# led-esp32.net
KiCad netlist of a schematic drawn in Altium Designer
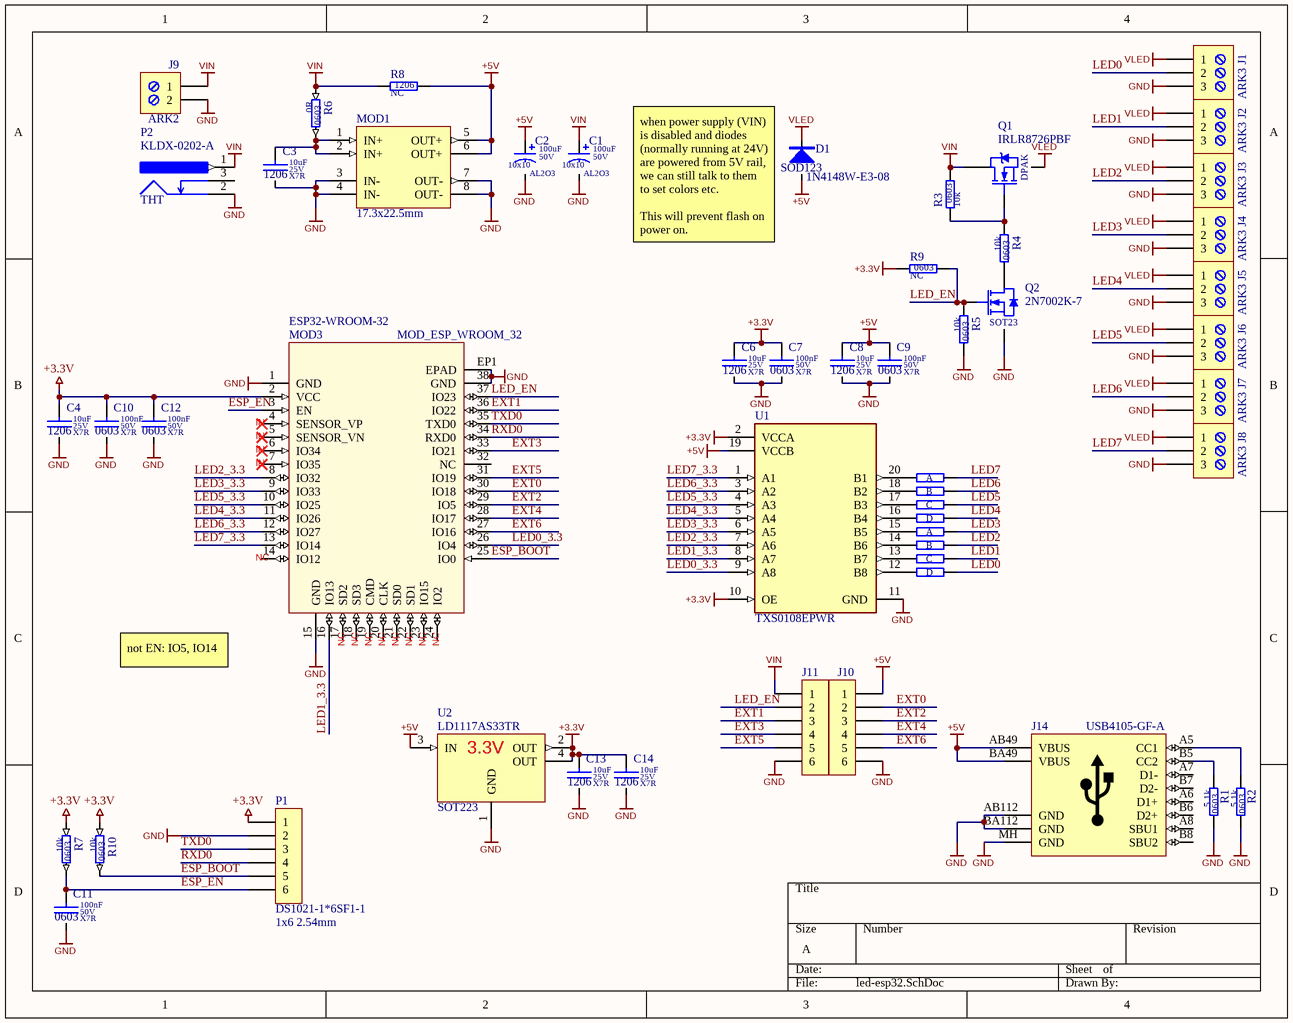
[diagram p0: led-esp32.SchDoc]

(export (version "E")
  (design (tool "Eeschema 10.0.6"))
  (components
    (comp (ref "C1")
      (value "100uF")
      (footprint "CE_D_10x10_SMD")
      (description "Polarized Capacitor")
      (fields
        (field (name "DIELECTRIC") "AL2O3")
        (field (name "SCH_FOOTPRINT") "10x10")
        (field (name "VOLTAGE") "50V")
        (field (name "PART NUMBER") "CE_100uF_50V_AL2O3_10x10_20")
        (field (name "MANUFACTURER") "Nichicon")
      )
      (libsource (lib "Library") (part "CE"))
    )
    (comp (ref "C2")
      (value "100uF")
      (footprint "CE_D_10x10_SMD")
      (description "Polarized Capacitor")
      (fields
        (field (name "DIELECTRIC") "AL2O3")
        (field (name "SCH_FOOTPRINT") "10x10")
        (field (name "VOLTAGE") "50V")
        (field (name "PART NUMBER") "CE_100uF_50V_AL2O3_10x10_20")
        (field (name "MANUFACTURER") "Nichicon")
      )
      (libsource (lib "Library") (part "CE"))
    )
    (comp (ref "C3")
      (value "10uF")
      (footprint "C_1206_3216")
      (description "Capacitor")
      (fields
        (field (name "DIELECTRIC") "X7R")
        (field (name "VOLTAGE") "25V")
        (field (name "SCH_FOOTPRINT") "1206")
        (field (name "PART NUMBER") "C_10uF_25V_X7R_1206_10")
        (field (name "MANUFACTURER") "Samsung")
      )
      (libsource (lib "Library") (part "C"))
    )
    (comp (ref "C4")
      (value "10uF")
      (footprint "C_1206_3216")
      (description "Capacitor")
      (fields
        (field (name "DIELECTRIC") "X7R")
        (field (name "VOLTAGE") "25V")
        (field (name "SCH_FOOTPRINT") "1206")
        (field (name "PART NUMBER") "C_10uF_25V_X7R_1206_10")
        (field (name "MANUFACTURER") "Samsung")
      )
      (libsource (lib "Library") (part "C"))
    )
    (comp (ref "C6")
      (value "10uF")
      (footprint "C_1206_3216")
      (description "Capacitor")
      (fields
        (field (name "DIELECTRIC") "X7R")
        (field (name "VOLTAGE") "25V")
        (field (name "SCH_FOOTPRINT") "1206")
        (field (name "PART NUMBER") "C_10uF_25V_X7R_1206_10")
        (field (name "MANUFACTURER") "Samsung")
      )
      (libsource (lib "Library") (part "C"))
    )
    (comp (ref "C7")
      (value "100nF")
      (footprint "C_0603_1608")
      (description "Capacitor")
      (fields
        (field (name "DIELECTRIC") "X7R")
        (field (name "VOLTAGE") "50V")
        (field (name "SCH_FOOTPRINT") "0603")
        (field (name "PART NUMBER") "C_100nF_50V_X7R_0603_5")
        (field (name "MANUFACTURER") "Samsung")
      )
      (libsource (lib "Library") (part "C"))
    )
    (comp (ref "C8")
      (value "10uF")
      (footprint "C_1206_3216")
      (description "Capacitor")
      (fields
        (field (name "DIELECTRIC") "X7R")
        (field (name "VOLTAGE") "25V")
        (field (name "SCH_FOOTPRINT") "1206")
        (field (name "PART NUMBER") "C_10uF_25V_X7R_1206_10")
        (field (name "MANUFACTURER") "Samsung")
      )
      (libsource (lib "Library") (part "C"))
    )
    (comp (ref "C9")
      (value "100nF")
      (footprint "C_0603_1608")
      (description "Capacitor")
      (fields
        (field (name "DIELECTRIC") "X7R")
        (field (name "VOLTAGE") "50V")
        (field (name "SCH_FOOTPRINT") "0603")
        (field (name "PART NUMBER") "C_100nF_50V_X7R_0603_5")
        (field (name "MANUFACTURER") "Samsung")
      )
      (libsource (lib "Library") (part "C"))
    )
    (comp (ref "C10")
      (value "100nF")
      (footprint "C_0603_1608")
      (description "Capacitor")
      (fields
        (field (name "DIELECTRIC") "X7R")
        (field (name "VOLTAGE") "50V")
        (field (name "SCH_FOOTPRINT") "0603")
        (field (name "PART NUMBER") "C_100nF_50V_X7R_0603_5")
        (field (name "MANUFACTURER") "Samsung")
      )
      (libsource (lib "Library") (part "C"))
    )
    (comp (ref "C11")
      (value "100nF")
      (footprint "C_0603_1608")
      (description "Capacitor")
      (fields
        (field (name "DIELECTRIC") "X7R")
        (field (name "VOLTAGE") "50V")
        (field (name "SCH_FOOTPRINT") "0603")
        (field (name "PART NUMBER") "C_100nF_50V_X7R_0603_5")
        (field (name "MANUFACTURER") "Samsung")
      )
      (libsource (lib "Library") (part "C"))
    )
    (comp (ref "C12")
      (value "100nF")
      (footprint "C_0603_1608")
      (description "Capacitor")
      (fields
        (field (name "DIELECTRIC") "X7R")
        (field (name "VOLTAGE") "50V")
        (field (name "SCH_FOOTPRINT") "0603")
        (field (name "PART NUMBER") "C_100nF_50V_X7R_0603_5")
        (field (name "MANUFACTURER") "Samsung")
      )
      (libsource (lib "Library") (part "C"))
    )
    (comp (ref "C13")
      (value "10uF")
      (footprint "C_1206_3216")
      (description "Capacitor")
      (fields
        (field (name "DIELECTRIC") "X7R")
        (field (name "VOLTAGE") "25V")
        (field (name "SCH_FOOTPRINT") "1206")
        (field (name "PART NUMBER") "C_10uF_25V_X7R_1206_10")
        (field (name "MANUFACTURER") "Samsung")
      )
      (libsource (lib "Library") (part "C"))
    )
    (comp (ref "C14")
      (value "10uF")
      (footprint "C_1206_3216")
      (description "Capacitor")
      (fields
        (field (name "DIELECTRIC") "X7R")
        (field (name "VOLTAGE") "25V")
        (field (name "SCH_FOOTPRINT") "1206")
        (field (name "PART NUMBER") "C_10uF_25V_X7R_1206_10")
        (field (name "MANUFACTURER") "Samsung")
      )
      (libsource (lib "Library") (part "C"))
    )
    (comp (ref "D1")
      (value "1N4148W-E3-08")
      (footprint "SOD123")
      (fields
        (field (name "SCH_FOOTPRINT") "SOD123")
        (field (name "PART NUMBER") "D_1N4148W_0A15_75V_SOD123")
        (field (name "VOLTAGE") "75")
        (field (name "MANUFACTURER") "Vishay")
      )
      (libsource (lib "Library") (part "D"))
    )
    (comp (ref "J1")
      (value "ARK3")
      (footprint "J_ARK3")
      (description "ARK Screw terminal, 3-Pin")
      (fields
        (field (name "SCH_FOOTPRINT") "ARK3")
        (field (name "PART NUMBER") "J_TB-5.0-P-3P")
        (field (name "MANUFACTURER") "DEGSON ELECTRONICS")
      )
      (libsource (lib "Library") (part "J_ARK3"))
    )
    (comp (ref "J2")
      (value "ARK3")
      (footprint "J_ARK3")
      (description "ARK Screw terminal, 3-Pin")
      (fields
        (field (name "SCH_FOOTPRINT") "ARK3")
        (field (name "PART NUMBER") "J_TB-5.0-P-3P")
        (field (name "MANUFACTURER") "DEGSON ELECTRONICS")
      )
      (libsource (lib "Library") (part "J_ARK3"))
    )
    (comp (ref "J3")
      (value "ARK3")
      (footprint "J_ARK3")
      (description "ARK Screw terminal, 3-Pin")
      (fields
        (field (name "SCH_FOOTPRINT") "ARK3")
        (field (name "PART NUMBER") "J_TB-5.0-P-3P")
        (field (name "MANUFACTURER") "DEGSON ELECTRONICS")
      )
      (libsource (lib "Library") (part "J_ARK3"))
    )
    (comp (ref "J4")
      (value "ARK3")
      (footprint "J_ARK3")
      (description "ARK Screw terminal, 3-Pin")
      (fields
        (field (name "SCH_FOOTPRINT") "ARK3")
        (field (name "PART NUMBER") "J_TB-5.0-P-3P")
        (field (name "MANUFACTURER") "DEGSON ELECTRONICS")
      )
      (libsource (lib "Library") (part "J_ARK3"))
    )
    (comp (ref "J5")
      (value "ARK3")
      (footprint "J_ARK3")
      (description "ARK Screw terminal, 3-Pin")
      (fields
        (field (name "SCH_FOOTPRINT") "ARK3")
        (field (name "PART NUMBER") "J_TB-5.0-P-3P")
        (field (name "MANUFACTURER") "DEGSON ELECTRONICS")
      )
      (libsource (lib "Library") (part "J_ARK3"))
    )
    (comp (ref "J6")
      (value "ARK3")
      (footprint "J_ARK3")
      (description "ARK Screw terminal, 3-Pin")
      (fields
        (field (name "SCH_FOOTPRINT") "ARK3")
        (field (name "PART NUMBER") "J_TB-5.0-P-3P")
        (field (name "MANUFACTURER") "DEGSON ELECTRONICS")
      )
      (libsource (lib "Library") (part "J_ARK3"))
    )
    (comp (ref "J7")
      (value "ARK3")
      (footprint "J_ARK3")
      (description "ARK Screw terminal, 3-Pin")
      (fields
        (field (name "SCH_FOOTPRINT") "ARK3")
        (field (name "PART NUMBER") "J_TB-5.0-P-3P")
        (field (name "MANUFACTURER") "DEGSON ELECTRONICS")
      )
      (libsource (lib "Library") (part "J_ARK3"))
    )
    (comp (ref "J8")
      (value "ARK3")
      (footprint "J_ARK3")
      (description "ARK Screw terminal, 3-Pin")
      (fields
        (field (name "SCH_FOOTPRINT") "ARK3")
        (field (name "PART NUMBER") "J_TB-5.0-P-3P")
        (field (name "MANUFACTURER") "DEGSON ELECTRONICS")
      )
      (libsource (lib "Library") (part "J_ARK3"))
    )
    (comp (ref "J9")
      (value "ARK2")
      (footprint "J_ARK2")
      (description "ARK Screw terminal, 2-Pin")
      (fields
        (field (name "SCH_FOOTPRINT") "ARK2")
        (field (name "PART NUMBER") "J_TB-5.0-P-2P")
        (field (name "MANUFACTURER") "DEGSON ELECTRONICS")
      )
      (libsource (lib "Library") (part "J_ARK2"))
    )
    (comp (ref "J10")
      (value "Goldpin female straight")
      (footprint "J_HEADER_1x6_2.54_VERTICAL")
      (description "Pin Header")
      (fields
        (field (name "PART NUMBER") "J_HEADER_1x6_2.54_VERTICAL")
        (field (name "MANUFACTURER") "Connfly")
      )
      (libsource (lib "Library") (part "J_HEADER_1x6"))
    )
    (comp (ref "J11")
      (value "Goldpin female straight")
      (footprint "J_HEADER_1x6_2.54_VERTICAL")
      (description "Pin Header")
      (fields
        (field (name "PART NUMBER") "J_HEADER_1x6_2.54_VERTICAL")
        (field (name "MANUFACTURER") "Connfly")
      )
      (libsource (lib "") (part "J_HEADER_1x6_1"))
    )
    (comp (ref "J14")
      (value "USB4105-GF-A")
      (footprint "J_USB_C_USB4105")
      (fields
        (field (name "PART NUMBER") "J_USB_C_USB4105-GF-A")
        (field (name "MANUFACTURER") "GCT")
        (field (name "Comment") "USB C Connector")
      )
      (libsource (lib "Library") (part "J_USB_C_2.0_USB4105"))
    )
    (comp (ref "MOD1")
      (value "Low cost, Aliexpress-ready DC-DC buck converter using MP1584")
      (footprint "MOD_BUCK_MP1584")
      (fields (field (name "SCH_FOOTPRINT") "17.3x22.5mm") (field (name "PART NUMBER") "MOD_BUCK_MP1584"))
      (libsource (lib "Library") (part "MOD_BUCK_MP1584"))
    )
    (comp (ref "MOD3")
      (value "ESP32-WROOM-32")
      (footprint "MOD_ESP_WROOM_32")
      (fields
        (field (name "SCH_FOOTPRINT") "MOD_ESP_WROOM_32")
        (field (name "PART NUMBER") "MOD_ESP32-WROOM-32")
        (field (name "MANUFACTURER") "ESPRESSIF")
        (field (name "Comment") "2.4 GHz Wi-Fi-and-Bluetooth combo chip")
      )
      (libsource (lib "Library") (part "MOD_ESP_WROOM_32"))
    )
    (comp (ref "P1")
      (value "DS1021-1*6SF1-1")
      (footprint "P_HEADER_1x6_2.54")
      (description "Pin Header")
      (fields
        (field (name "PART NUMBER") "P_HEADER_1x6_2.54")
        (field (name "SCH_FOOTPRINT") "1x6 2.54mm")
        (field (name "MANUFACTURER") "Connfly")
      )
      (libsource (lib "Library") (part "P_HEADER_1x6"))
    )
    (comp (ref "P2")
      (value "KLDX-0202-A")
      (footprint "P_KLDX-0202-A")
      (description "Typical 3-pin jack power connector with switch")
      (fields
        (field (name "SCH_FOOTPRINT") "THT")
        (field (name "PART NUMBER") "P_KLDX-0202-A")
        (field (name "MANUFACTURER") "Kycon")
      )
      (libsource (lib "Library") (part "P_DC_JACK"))
    )
    (comp (ref "Q1")
      (value "IRLR8726PBF")
      (footprint "DPAK_TO252-3_SC63_M")
      (fields
        (field (name "SCH_FOOTPRINT") "DPAK")
        (field (name "PART NUMBER") "QNS_IRLR8726PBF")
        (field (name "VOLTAGE") "30V")
        (field (name "MANUFACTURER") "Infineon")
      )
      (libsource (lib "Library") (part "QNS_GDS"))
    )
    (comp (ref "Q2")
      (value "2N7002K-7")
      (footprint "SOT23_TO236_SC59")
      (fields
        (field (name "SCH_FOOTPRINT") "SOT23")
        (field (name "PART NUMBER") "QN_2N7002K-7")
        (field (name "VOLTAGE") "60V")
        (field (name "MANUFACTURER") "Diodes Inc")
      )
      (libsource (lib "Library") (part "QN_GSD"))
    )
    (comp (ref "R1")
      (value "5.1k")
      (footprint "R_0603_1608")
      (fields
        (field (name "SCH_FOOTPRINT") "0603")
        (field (name "PART NUMBER") "R_5.1k_0603_1")
        (field (name "VOLTAGE") "75V")
        (field (name "POWER") "100mW")
      )
      (libsource (lib "") (part "R_1"))
    )
    (comp (ref "R2")
      (value "5.1k")
      (footprint "R_0603_1608")
      (fields
        (field (name "SCH_FOOTPRINT") "0603")
        (field (name "PART NUMBER") "R_5.1k_0603_1")
        (field (name "VOLTAGE") "75V")
        (field (name "POWER") "100mW")
      )
      (libsource (lib "") (part "R_1"))
    )
    (comp (ref "R3")
      (value "10k")
      (footprint "R_0603_1608")
      (fields
        (field (name "SCH_FOOTPRINT") "0603")
        (field (name "PART NUMBER") "R_10k_0603_1")
        (field (name "VOLTAGE") "75V")
        (field (name "POWER") "100mW")
      )
      (libsource (lib "") (part "R_1"))
    )
    (comp (ref "R4")
      (value "10k")
      (footprint "R_0603_1608")
      (fields
        (field (name "SCH_FOOTPRINT") "0603")
        (field (name "PART NUMBER") "R_10k_0603_1")
        (field (name "VOLTAGE") "75V")
        (field (name "POWER") "100mW")
      )
      (libsource (lib "") (part "R_1"))
    )
    (comp (ref "R5")
      (value "10k")
      (footprint "R_0603_1608")
      (fields
        (field (name "SCH_FOOTPRINT") "0603")
        (field (name "PART NUMBER") "R_10k_0603_1")
        (field (name "VOLTAGE") "75V")
        (field (name "POWER") "100mW")
      )
      (libsource (lib "") (part "R_1"))
    )
    (comp (ref "R6")
      (value "0R")
      (footprint "R_0603_1608")
      (fields
        (field (name "SCH_FOOTPRINT") "0603")
        (field (name "PART NUMBER") "R_0R_0603_1")
        (field (name "VOLTAGE") "75V")
        (field (name "POWER") "100mW")
      )
      (libsource (lib "Library") (part "R"))
    )
    (comp (ref "R7")
      (value "10k")
      (footprint "R_0603_1608")
      (fields
        (field (name "SCH_FOOTPRINT") "0603")
        (field (name "PART NUMBER") "R_10k_0603_1_AECQ0")
        (field (name "VOLTAGE") "75V")
        (field (name "POWER") "100mW")
      )
      (libsource (lib "Library") (part "R"))
    )
    (comp (ref "R8")
      (value "NC")
      (footprint "R_NC_1206_3216")
      (fields
        (field (name "SCH_FOOTPRINT") "1206")
        (field (name "PART NUMBER") "R_GENERIC_1206")
        (field (name "Comment") "Resistor")
      )
      (libsource (lib "") (part "R_1"))
    )
    (comp (ref "R9")
      (value "NC")
      (footprint "R_NC_0603_1608")
      (fields
        (field (name "SCH_FOOTPRINT") "0603")
        (field (name "PART NUMBER") "R_GENERIC_0603")
        (field (name "Comment") "Resistor")
      )
      (libsource (lib "") (part "R_1"))
    )
    (comp (ref "R10")
      (value "10k")
      (footprint "R_0603_1608")
      (fields
        (field (name "SCH_FOOTPRINT") "0603")
        (field (name "PART NUMBER") "R_10k_0603_1_AECQ0")
        (field (name "VOLTAGE") "75V")
        (field (name "POWER") "100mW")
      )
      (libsource (lib "Library") (part "R"))
    )
    (comp (ref "RN1")
      (value "Resistors Network")
      (footprint "RN4_0804_2010")
      (fields
        (field (name "PART NUMBER") "RN4_120R_0804_5")
        (field (name "VOLTAGE") "50V")
        (field (name "POWER") "63mW")
      )
      (libsource (lib "Library") (part "RN4"))
    )
    (comp (ref "RN2")
      (value "Resistors Network")
      (footprint "RN4_0804_2010")
      (fields
        (field (name "PART NUMBER") "RN4_120R_0804_5")
        (field (name "VOLTAGE") "50V")
        (field (name "POWER") "63mW")
      )
      (libsource (lib "Library") (part "RN4"))
    )
    (comp (ref "U1")
      (value "TXS0108EPWR")
      (footprint "FP-PW0020A-IPC_C")
      (description "IC TRNSLTR BIDIRECTIONAL 20TSSOP")
      (libsource (lib "Altium Content Vault") (part "86128ddf5852d4e934b2dd0188c13f1"))
    )
    (comp (ref "U2")
      (value "LD1117AS33TR")
      (footprint "SOT223_SC73")
      (description "typical configuration")
      (fields
        (field (name "SCH_FOOTPRINT") "SOT223")
        (field (name "PART NUMBER") "VL_LD1117AS33TR_3V3_1A2")
        (field (name "VOLTAGE") "3.3V")
      )
      (libsource (lib "Library") (part "VL_4pin_3_1_2,4"))
    )
  )
  (nets
    (net (code "1") (name "+3.3V") (class "Default")
      (node (ref "C10") (pin "1") (pinfunction "1_1") (pintype "passive"))
      (node (ref "C12") (pin "1") (pinfunction "1_1") (pintype "passive"))
      (node (ref "C13") (pin "1") (pinfunction "1_1") (pintype "passive"))
      (node (ref "C14") (pin "1") (pinfunction "1_1") (pintype "passive"))
      (node (ref "C4") (pin "1") (pinfunction "1_1") (pintype "passive"))
      (node (ref "C6") (pin "1") (pinfunction "1_1") (pintype "passive"))
      (node (ref "C7") (pin "1") (pinfunction "1_1") (pintype "passive"))
      (node (ref "MOD3") (pin "2") (pinfunction "VCC_2") (pintype "input"))
      (node (ref "P1") (pin "1") (pinfunction "1_1") (pintype "passive"))
      (node (ref "R10") (pin "1") (pinfunction "1_1") (pintype "input"))
      (node (ref "R7") (pin "1") (pinfunction "1_1") (pintype "input"))
      (node (ref "R9") (pin "1") (pinfunction "1_1") (pintype "passive"))
      (node (ref "U1") (pin "10") (pinfunction "OE_10") (pintype "input"))
      (node (ref "U1") (pin "2") (pinfunction "VCCA_2") (pintype "power_in"))
      (node (ref "U2") (pin "2") (pinfunction "OUT_2") (pintype "output"))
      (node (ref "U2") (pin "4") (pinfunction "OUT_4") (pintype "passive"))
    )
    (net (code "2") (name "+5V") (class "Default")
      (node (ref "C2") (pin "1") (pinfunction "1_1") (pintype "passive"))
      (node (ref "C8") (pin "1") (pinfunction "1_1") (pintype "passive"))
      (node (ref "C9") (pin "1") (pinfunction "1_1") (pintype "passive"))
      (node (ref "D1") (pin "2") (pintype "passive"))
      (node (ref "J10") (pin "1") (pinfunction "1_1") (pintype "passive"))
      (node (ref "J14") (pin "AB49") (pinfunction "VBUS_AB49") (pintype "power_in"))
      (node (ref "J14") (pin "BA49") (pinfunction "VBUS_BA49") (pintype "power_in"))
      (node (ref "MOD1") (pin "5") (pinfunction "OUT+_5") (pintype "output"))
      (node (ref "MOD1") (pin "6") (pinfunction "OUT+_6") (pintype "passive"))
      (node (ref "R8") (pin "2") (pinfunction "2_2") (pintype "passive"))
      (node (ref "U1") (pin "19") (pinfunction "VCCB_19") (pintype "power_in"))
      (node (ref "U2") (pin "3") (pinfunction "IN_3") (pintype "input"))
    )
    (net (code "3") (name "/ESP_BOOT") (class "Default")
      (node (ref "MOD3") (pin "25") (pinfunction "IO0_25") (pintype "input"))
      (node (ref "P1") (pin "5") (pinfunction "5_5") (pintype "passive"))
      (node (ref "R10") (pin "2") (pinfunction "2_2") (pintype "output"))
    )
    (net (code "4") (name "/ESP_EN") (class "Default")
      (node (ref "C11") (pin "1") (pinfunction "1_1") (pintype "passive"))
      (node (ref "MOD3") (pin "3") (pinfunction "EN_3") (pintype "input"))
      (node (ref "P1") (pin "6") (pinfunction "6_6") (pintype "passive"))
      (node (ref "R7") (pin "2") (pinfunction "2_2") (pintype "output"))
    )
    (net (code "5") (name "/EXT0") (class "Default")
      (node (ref "J10") (pin "2") (pinfunction "2_2") (pintype "passive"))
      (node (ref "MOD3") (pin "30") (pinfunction "IO18_30") (pintype "bidirectional"))
    )
    (net (code "6") (name "/EXT1") (class "Default")
      (node (ref "J11") (pin "3") (pinfunction "3_3") (pintype "passive"))
      (node (ref "MOD3") (pin "36") (pinfunction "IO22_36") (pintype "bidirectional"))
    )
    (net (code "7") (name "/EXT2") (class "Default")
      (node (ref "J10") (pin "3") (pinfunction "3_3") (pintype "passive"))
      (node (ref "MOD3") (pin "29") (pinfunction "IO5_29") (pintype "bidirectional"))
    )
    (net (code "8") (name "/EXT3") (class "Default")
      (node (ref "J11") (pin "4") (pinfunction "4_4") (pintype "passive"))
      (node (ref "MOD3") (pin "33") (pinfunction "IO21_33") (pintype "bidirectional"))
    )
    (net (code "9") (name "/EXT4") (class "Default")
      (node (ref "J10") (pin "4") (pinfunction "4_4") (pintype "passive"))
      (node (ref "MOD3") (pin "28") (pinfunction "IO17_28") (pintype "bidirectional"))
    )
    (net (code "10") (name "/EXT5") (class "Default")
      (node (ref "J11") (pin "5") (pinfunction "5_5") (pintype "passive"))
      (node (ref "MOD3") (pin "31") (pinfunction "IO19_31") (pintype "bidirectional"))
    )
    (net (code "11") (name "/EXT6") (class "Default")
      (node (ref "J10") (pin "5") (pinfunction "5_5") (pintype "passive"))
      (node (ref "MOD3") (pin "27") (pinfunction "IO16_27") (pintype "bidirectional"))
    )
    (net (code "12") (name "/LED0") (class "Default")
      (node (ref "J1") (pin "2") (pinfunction "2_2") (pintype "passive"))
      (node (ref "RN2") (pin "5") (pinfunction "5_5") (pintype "passive"))
    )
    (net (code "13") (name "/LED0_3.3") (class "Default")
      (node (ref "MOD3") (pin "26") (pinfunction "IO4_26") (pintype "bidirectional"))
      (node (ref "U1") (pin "9") (pinfunction "A8_9") (pintype "input"))
    )
    (net (code "14") (name "/LED1") (class "Default")
      (node (ref "J2") (pin "2") (pinfunction "2_2") (pintype "passive"))
      (node (ref "RN2") (pin "6") (pinfunction "6_6") (pintype "passive"))
    )
    (net (code "15") (name "/LED1_3.3") (class "Default")
      (node (ref "MOD3") (pin "16") (pinfunction "IO13_16") (pintype "bidirectional"))
      (node (ref "U1") (pin "8") (pinfunction "A7_8") (pintype "input"))
    )
    (net (code "16") (name "/LED2") (class "Default")
      (node (ref "J3") (pin "2") (pinfunction "2_2") (pintype "passive"))
      (node (ref "RN2") (pin "7") (pinfunction "7_7") (pintype "passive"))
    )
    (net (code "17") (name "/LED2_3.3") (class "Default")
      (node (ref "MOD3") (pin "8") (pinfunction "IO32_8") (pintype "bidirectional"))
      (node (ref "U1") (pin "7") (pinfunction "A6_7") (pintype "input"))
    )
    (net (code "18") (name "/LED3") (class "Default")
      (node (ref "J4") (pin "2") (pinfunction "2_2") (pintype "passive"))
      (node (ref "RN2") (pin "8") (pinfunction "8_8") (pintype "passive"))
    )
    (net (code "19") (name "/LED3_3.3") (class "Default")
      (node (ref "MOD3") (pin "9") (pinfunction "IO33_9") (pintype "bidirectional"))
      (node (ref "U1") (pin "6") (pinfunction "A5_6") (pintype "input"))
    )
    (net (code "20") (name "/LED4") (class "Default")
      (node (ref "J5") (pin "2") (pinfunction "2_2") (pintype "passive"))
      (node (ref "RN1") (pin "5") (pinfunction "5_5") (pintype "passive"))
    )
    (net (code "21") (name "/LED4_3.3") (class "Default")
      (node (ref "MOD3") (pin "11") (pinfunction "IO26_11") (pintype "bidirectional"))
      (node (ref "U1") (pin "5") (pinfunction "A4_5") (pintype "input"))
    )
    (net (code "22") (name "/LED5") (class "Default")
      (node (ref "J6") (pin "2") (pinfunction "2_2") (pintype "passive"))
      (node (ref "RN1") (pin "6") (pinfunction "6_6") (pintype "passive"))
    )
    (net (code "23") (name "/LED5_3.3") (class "Default")
      (node (ref "MOD3") (pin "10") (pinfunction "IO25_10") (pintype "bidirectional"))
      (node (ref "U1") (pin "4") (pinfunction "A3_4") (pintype "input"))
    )
    (net (code "24") (name "/LED6") (class "Default")
      (node (ref "J7") (pin "2") (pinfunction "2_2") (pintype "passive"))
      (node (ref "RN1") (pin "7") (pinfunction "7_7") (pintype "passive"))
    )
    (net (code "25") (name "/LED6_3.3") (class "Default")
      (node (ref "MOD3") (pin "12") (pinfunction "IO27_12") (pintype "bidirectional"))
      (node (ref "U1") (pin "3") (pinfunction "A2_3") (pintype "input"))
    )
    (net (code "26") (name "/LED7") (class "Default")
      (node (ref "J8") (pin "2") (pinfunction "2_2") (pintype "passive"))
      (node (ref "RN1") (pin "8") (pinfunction "8_8") (pintype "passive"))
    )
    (net (code "27") (name "/LED7_3.3") (class "Default")
      (node (ref "MOD3") (pin "13") (pinfunction "IO14_13") (pintype "bidirectional"))
      (node (ref "U1") (pin "1") (pinfunction "A1_1") (pintype "input"))
    )
    (net (code "28") (name "/LED_EN") (class "Default")
      (node (ref "J11") (pin "2") (pinfunction "2_2") (pintype "passive"))
      (node (ref "MOD3") (pin "37") (pinfunction "IO23_37") (pintype "bidirectional"))
      (node (ref "Q2") (pin "1") (pinfunction "G_1") (pintype "passive"))
      (node (ref "R5") (pin "1") (pinfunction "1_1") (pintype "passive"))
      (node (ref "R9") (pin "2") (pinfunction "2_2") (pintype "passive"))
    )
    (net (code "29") (name "/RXD0") (class "Default")
      (node (ref "MOD3") (pin "34") (pinfunction "RXD0_34") (pintype "bidirectional"))
      (node (ref "P1") (pin "4") (pinfunction "4_4") (pintype "passive"))
    )
    (net (code "30") (name "/TXD0") (class "Default")
      (node (ref "MOD3") (pin "35") (pinfunction "TXD0_35") (pintype "bidirectional"))
      (node (ref "P1") (pin "3") (pinfunction "3_3") (pintype "passive"))
    )
    (net (code "31") (name "GND") (class "Default")
      (node (ref "C1") (pin "2") (pinfunction "2_2") (pintype "passive"))
      (node (ref "C10") (pin "2") (pinfunction "2_2") (pintype "passive"))
      (node (ref "C11") (pin "2") (pinfunction "2_2") (pintype "passive"))
      (node (ref "C12") (pin "2") (pinfunction "2_2") (pintype "passive"))
      (node (ref "C13") (pin "2") (pinfunction "2_2") (pintype "passive"))
      (node (ref "C14") (pin "2") (pinfunction "2_2") (pintype "passive"))
      (node (ref "C2") (pin "2") (pinfunction "2_2") (pintype "passive"))
      (node (ref "C3") (pin "2") (pinfunction "2_2") (pintype "passive"))
      (node (ref "C4") (pin "2") (pinfunction "2_2") (pintype "passive"))
      (node (ref "C6") (pin "2") (pinfunction "2_2") (pintype "passive"))
      (node (ref "C7") (pin "2") (pinfunction "2_2") (pintype "passive"))
      (node (ref "C8") (pin "2") (pinfunction "2_2") (pintype "passive"))
      (node (ref "C9") (pin "2") (pinfunction "2_2") (pintype "passive"))
      (node (ref "J1") (pin "3") (pinfunction "3_3") (pintype "passive"))
      (node (ref "J10") (pin "6") (pinfunction "6_6") (pintype "passive"))
      (node (ref "J11") (pin "6") (pinfunction "6_6") (pintype "passive"))
      (node (ref "J14") (pin "AB112") (pinfunction "GND_AB112") (pintype "power_in"))
      (node (ref "J14") (pin "BA112") (pinfunction "GND_BA112") (pintype "power_in"))
      (node (ref "J14") (pin "MH") (pinfunction "GND_MH") (pintype "power_in"))
      (node (ref "J2") (pin "3") (pinfunction "3_3") (pintype "passive"))
      (node (ref "J3") (pin "3") (pinfunction "3_3") (pintype "passive"))
      (node (ref "J4") (pin "3") (pinfunction "3_3") (pintype "passive"))
      (node (ref "J5") (pin "3") (pinfunction "3_3") (pintype "passive"))
      (node (ref "J6") (pin "3") (pinfunction "3_3") (pintype "passive"))
      (node (ref "J7") (pin "3") (pinfunction "3_3") (pintype "passive"))
      (node (ref "J8") (pin "3") (pinfunction "3_3") (pintype "passive"))
      (node (ref "J9") (pin "2") (pinfunction "2_2") (pintype "passive"))
      (node (ref "MOD1") (pin "3") (pinfunction "IN-_3") (pintype "power_in"))
      (node (ref "MOD1") (pin "4") (pinfunction "IN-_4") (pintype "power_in"))
      (node (ref "MOD1") (pin "7") (pinfunction "OUT-_7") (pintype "output"))
      (node (ref "MOD1") (pin "8") (pinfunction "OUT-_8") (pintype "passive"))
      (node (ref "MOD3") (pin "1") (pinfunction "GND_1") (pintype "power_in"))
      (node (ref "MOD3") (pin "15") (pinfunction "GND_15") (pintype "power_in"))
      (node (ref "MOD3") (pin "38") (pinfunction "GND_38") (pintype "power_in"))
      (node (ref "MOD3") (pin "EP1") (pinfunction "EPAD_EP1") (pintype "power_in"))
      (node (ref "P1") (pin "2") (pinfunction "2_2") (pintype "passive"))
      (node (ref "P2") (pin "2") (pinfunction "2_2") (pintype "passive"))
      (node (ref "Q2") (pin "2") (pinfunction "S_2") (pintype "passive"))
      (node (ref "R1") (pin "2") (pinfunction "2_2") (pintype "passive"))
      (node (ref "R2") (pin "2") (pinfunction "2_2") (pintype "passive"))
      (node (ref "R5") (pin "2") (pinfunction "2_2") (pintype "passive"))
      (node (ref "U1") (pin "11") (pinfunction "GND_11") (pintype "power_in"))
      (node (ref "U2") (pin "1") (pinfunction "GND_1") (pintype "power_in"))
    )
    (net (code "32") (name "Net-(C3-Pad1)") (class "Default")
      (node (ref "C3") (pin "1") (pinfunction "1_1") (pintype "passive"))
      (node (ref "MOD1") (pin "1") (pinfunction "IN+_1") (pintype "input"))
      (node (ref "MOD1") (pin "2") (pinfunction "IN+_2") (pintype "input"))
      (node (ref "R6") (pin "2") (pinfunction "2_2") (pintype "output"))
    )
    (net (code "33") (name "Net-(J14-CC1)") (class "Default")
      (node (ref "J14") (pin "A5") (pinfunction "CC1_A5") (pintype "bidirectional"))
      (node (ref "R2") (pin "1") (pinfunction "1_1") (pintype "passive"))
    )
    (net (code "34") (name "Net-(J14-CC2)") (class "Default")
      (node (ref "J14") (pin "B5") (pinfunction "CC2_B5") (pintype "bidirectional"))
      (node (ref "R1") (pin "1") (pinfunction "1_1") (pintype "passive"))
    )
    (net (code "35") (name "Net-(Q1-G)") (class "Default")
      (node (ref "Q1") (pin "1") (pinfunction "G_1") (pintype "passive"))
      (node (ref "R3") (pin "1") (pinfunction "1_1") (pintype "passive"))
      (node (ref "R4") (pin "1") (pinfunction "1_1") (pintype "passive"))
    )
    (net (code "36") (name "Net-(Q2-D)") (class "Default")
      (node (ref "Q2") (pin "3") (pinfunction "D_3") (pintype "passive"))
      (node (ref "R4") (pin "2") (pinfunction "2_2") (pintype "passive"))
    )
    (net (code "37") (name "Net-(U1-B1)") (class "Default")
      (node (ref "RN1") (pin "1") (pinfunction "1_1") (pintype "passive"))
      (node (ref "U1") (pin "20") (pinfunction "B1_20") (pintype "output"))
    )
    (net (code "38") (name "Net-(U1-B2)") (class "Default")
      (node (ref "RN1") (pin "2") (pinfunction "2_2") (pintype "passive"))
      (node (ref "U1") (pin "18") (pinfunction "B2_18") (pintype "output"))
    )
    (net (code "39") (name "Net-(U1-B3)") (class "Default")
      (node (ref "RN1") (pin "3") (pinfunction "3_3") (pintype "passive"))
      (node (ref "U1") (pin "17") (pinfunction "B3_17") (pintype "output"))
    )
    (net (code "40") (name "Net-(U1-B4)") (class "Default")
      (node (ref "RN1") (pin "4") (pinfunction "4_4") (pintype "passive"))
      (node (ref "U1") (pin "16") (pinfunction "B4_16") (pintype "output"))
    )
    (net (code "41") (name "Net-(U1-B5)") (class "Default")
      (node (ref "RN2") (pin "1") (pinfunction "1_1") (pintype "passive"))
      (node (ref "U1") (pin "15") (pinfunction "B5_15") (pintype "output"))
    )
    (net (code "42") (name "Net-(U1-B6)") (class "Default")
      (node (ref "RN2") (pin "2") (pinfunction "2_2") (pintype "passive"))
      (node (ref "U1") (pin "14") (pinfunction "B6_14") (pintype "output"))
    )
    (net (code "43") (name "Net-(U1-B7)") (class "Default")
      (node (ref "RN2") (pin "3") (pinfunction "3_3") (pintype "passive"))
      (node (ref "U1") (pin "13") (pinfunction "B7_13") (pintype "output"))
    )
    (net (code "44") (name "Net-(U1-B8)") (class "Default")
      (node (ref "RN2") (pin "4") (pinfunction "4_4") (pintype "passive"))
      (node (ref "U1") (pin "12") (pinfunction "B8_12") (pintype "output"))
    )
    (net (code "45") (name "VIN") (class "Default")
      (node (ref "C1") (pin "1") (pinfunction "1_1") (pintype "passive"))
      (node (ref "J11") (pin "1") (pinfunction "1_1") (pintype "passive"))
      (node (ref "J9") (pin "1") (pinfunction "1_1") (pintype "passive"))
      (node (ref "P2") (pin "1") (pinfunction "1_1") (pintype "output"))
      (node (ref "Q1") (pin "2") (pinfunction "D_2") (pintype "passive"))
      (node (ref "R3") (pin "2") (pinfunction "2_2") (pintype "passive"))
      (node (ref "R6") (pin "1") (pinfunction "1_1") (pintype "input"))
      (node (ref "R8") (pin "1") (pinfunction "1_1") (pintype "passive"))
    )
    (net (code "46") (name "VLED") (class "Default")
      (node (ref "D1") (pin "1") (pintype "passive"))
      (node (ref "J1") (pin "1") (pinfunction "1_1") (pintype "passive"))
      (node (ref "J2") (pin "1") (pinfunction "1_1") (pintype "passive"))
      (node (ref "J3") (pin "1") (pinfunction "1_1") (pintype "passive"))
      (node (ref "J4") (pin "1") (pinfunction "1_1") (pintype "passive"))
      (node (ref "J5") (pin "1") (pinfunction "1_1") (pintype "passive"))
      (node (ref "J6") (pin "1") (pinfunction "1_1") (pintype "passive"))
      (node (ref "J7") (pin "1") (pinfunction "1_1") (pintype "passive"))
      (node (ref "J8") (pin "1") (pinfunction "1_1") (pintype "passive"))
      (node (ref "Q1") (pin "3") (pinfunction "S_3") (pintype "passive"))
    )
    (net (code "47") (name "unconnected-(J14-D1+-PadA6)") (class "Default")
      (node (ref "J14") (pin "A6") (pinfunction "D1+_A6") (pintype "bidirectional"))
    )
    (net (code "48") (name "unconnected-(J14-D1--PadA7)") (class "Default")
      (node (ref "J14") (pin "A7") (pinfunction "D1-_A7") (pintype "bidirectional"))
    )
    (net (code "49") (name "unconnected-(J14-D2+-PadB6)") (class "Default")
      (node (ref "J14") (pin "B6") (pinfunction "D2+_B6") (pintype "bidirectional"))
    )
    (net (code "50") (name "unconnected-(J14-D2--PadB7)") (class "Default")
      (node (ref "J14") (pin "B7") (pinfunction "D2-_B7") (pintype "bidirectional"))
    )
    (net (code "51") (name "unconnected-(J14-SBU1-PadA8)") (class "Default")
      (node (ref "J14") (pin "A8") (pinfunction "SBU1_A8") (pintype "bidirectional"))
    )
    (net (code "52") (name "unconnected-(J14-SBU2-PadB8)") (class "Default")
      (node (ref "J14") (pin "B8") (pinfunction "SBU2_B8") (pintype "bidirectional"))
    )
    (net (code "53") (name "unconnected-(MOD3-CLK-Pad20)") (class "Default")
      (node (ref "MOD3") (pin "20") (pinfunction "CLK_20") (pintype "bidirectional"))
    )
    (net (code "54") (name "unconnected-(MOD3-CMD-Pad19)") (class "Default")
      (node (ref "MOD3") (pin "19") (pinfunction "CMD_19") (pintype "bidirectional"))
    )
    (net (code "55") (name "unconnected-(MOD3-IO2-Pad24)") (class "Default")
      (node (ref "MOD3") (pin "24") (pinfunction "IO2_24") (pintype "bidirectional"))
    )
    (net (code "56") (name "unconnected-(MOD3-IO12-Pad14)") (class "Default")
      (node (ref "MOD3") (pin "14") (pinfunction "IO12_14") (pintype "bidirectional"))
    )
    (net (code "57") (name "unconnected-(MOD3-IO15-Pad23)") (class "Default")
      (node (ref "MOD3") (pin "23") (pinfunction "IO15_23") (pintype "bidirectional"))
    )
    (net (code "58") (name "unconnected-(MOD3-IO34-Pad6)") (class "Default")
      (node (ref "MOD3") (pin "6") (pinfunction "IO34_6") (pintype "input+no_connect"))
    )
    (net (code "59") (name "unconnected-(MOD3-IO35-Pad7)") (class "Default")
      (node (ref "MOD3") (pin "7") (pinfunction "IO35_7") (pintype "input+no_connect"))
    )
    (net (code "60") (name "unconnected-(MOD3-NC-Pad32)") (class "Default")
      (node (ref "MOD3") (pin "32") (pinfunction "NC_32") (pintype "passive"))
    )
    (net (code "61") (name "unconnected-(MOD3-SD0-Pad21)") (class "Default")
      (node (ref "MOD3") (pin "21") (pinfunction "SD0_21") (pintype "bidirectional"))
    )
    (net (code "62") (name "unconnected-(MOD3-SD1-Pad22)") (class "Default")
      (node (ref "MOD3") (pin "22") (pinfunction "SD1_22") (pintype "bidirectional"))
    )
    (net (code "63") (name "unconnected-(MOD3-SD2-Pad17)") (class "Default")
      (node (ref "MOD3") (pin "17") (pinfunction "SD2_17") (pintype "bidirectional"))
    )
    (net (code "64") (name "unconnected-(MOD3-SD3-Pad18)") (class "Default")
      (node (ref "MOD3") (pin "18") (pinfunction "SD3_18") (pintype "bidirectional"))
    )
    (net (code "65") (name "unconnected-(MOD3-SENSOR_VN-Pad5)") (class "Default")
      (node (ref "MOD3") (pin "5") (pinfunction "SENSOR_VN_5") (pintype "input+no_connect"))
    )
    (net (code "66") (name "unconnected-(MOD3-SENSOR_VP-Pad4)") (class "Default")
      (node (ref "MOD3") (pin "4") (pinfunction "SENSOR_VP_4") (pintype "input+no_connect"))
    )
    (net (code "67") (name "unconnected-(P2-Pad3)") (class "Default")
      (node (ref "P2") (pin "3") (pinfunction "3_3") (pintype "passive"))
    )
  )
)
